# KT1025A.net
KiCad netlist of a schematic drawn in Altium Designer
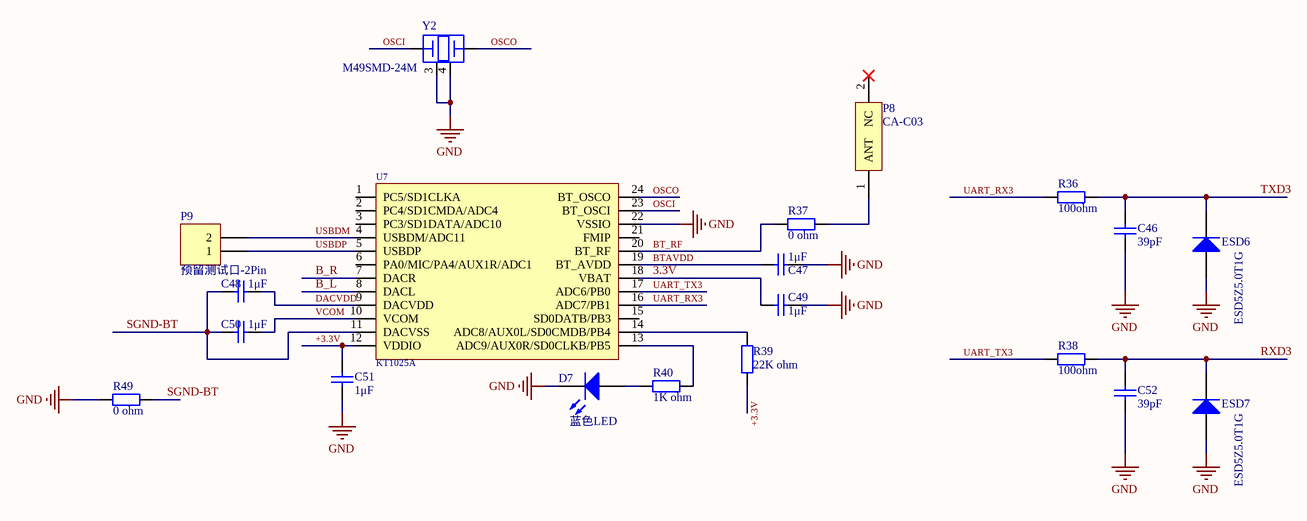
[diagram p0: KT1025A.SchDoc]

(export (version "E")
  (design (tool "Eeschema 10.0.6"))
  (components
    (comp (ref "C46")
      (value "39pF")
      (footprint "0603C")
      (description "39pF_50V,C0G (EIA),±1%")
      (libsource (lib "Yang_Lib") (part "Cap_39pF_50V_0603"))
    )
    (comp (ref "C47")
      (value "1μF")
      (footprint "0603C")
      (description "1μF_50V,X5R,±10%")
      (libsource (lib "Yang_Lib") (part "Cap_1μF_50V_0603"))
    )
    (comp (ref "C48")
      (value "1μF")
      (footprint "0603C")
      (description "1μF_50V,X5R,±10%")
      (libsource (lib "Yang_Lib") (part "Cap_1μF_50V_0603"))
    )
    (comp (ref "C49")
      (value "1μF")
      (footprint "0603C")
      (description "1μF_50V,X5R,±10%")
      (libsource (lib "Yang_Lib") (part "Cap_1μF_50V_0603"))
    )
    (comp (ref "C50")
      (value "1μF")
      (footprint "0603C")
      (description "1μF_50V,X5R,±10%")
      (libsource (lib "Yang_Lib") (part "Cap_1μF_50V_0603"))
    )
    (comp (ref "C51")
      (value "1μF")
      (footprint "0603C")
      (description "1μF_50V,X5R,±10%")
      (libsource (lib "Yang_Lib") (part "Cap_1μF_50V_0603"))
    )
    (comp (ref "C52")
      (value "39pF")
      (footprint "0603C")
      (description "39pF_50V,C0G (EIA),±1%")
      (libsource (lib "Yang_Lib") (part "Cap_39pF_50V_0603"))
    )
    (comp (ref "D7") (value "蓝色LED") (footprint "0603LED") (libsource (lib "Yang_Lib") (part "蓝色LED")))
    (comp (ref "ESD6")
      (value "ESD5Z5.0T1G")
      (footprint "SOD523")
      (libsource (lib "Yang_Lib") (part "ESD5Z5.0T1G_SOD523"))
    )
    (comp (ref "ESD7")
      (value "ESD5Z5.0T1G")
      (footprint "SOD523")
      (libsource (lib "Yang_Lib") (part "ESD5Z5.0T1G_SOD523"))
    )
    (comp (ref "P8") (value "CA-C03") (footprint "ANT") (libsource (lib "Yang_Lib") (part "CA-C03")))
    (comp (ref "P9")
      (value "预留测试口-2Pin")
      (footprint "预留测试口 2Pin")
      (libsource (lib "Yang_Lib") (part "预留测试口-2Pin"))
    )
    (comp (ref "R36")
      (value "100ohm")
      (footprint "0603R")
      (description "100 ohm_5%")
      (libsource (lib "Yang_Lib") (part "Res_100ohm_0603"))
    )
    (comp (ref "R37")
      (value "0 ohm")
      (footprint "0603R")
      (description "0 ohm,5%")
      (libsource (lib "Yang_Lib") (part "Res_0 ohm_0603"))
    )
    (comp (ref "R38")
      (value "100ohm")
      (footprint "0603R")
      (description "100 ohm_5%")
      (libsource (lib "Yang_Lib") (part "Res_100ohm_0603"))
    )
    (comp (ref "R39")
      (value "22K ohm")
      (footprint "0603R")
      (description "22K ohm,1%")
      (libsource (lib "Yang_Lib") (part "Res_22K ohm_0603"))
    )
    (comp (ref "R40")
      (value "1K ohm")
      (footprint "0603R")
      (description "1K ohm,1%")
      (libsource (lib "Yang_Lib") (part "Res_1K ohm_0603"))
    )
    (comp (ref "R49")
      (value "0 ohm")
      (footprint "0805R")
      (description "0 ohm,5%")
      (libsource (lib "Yang_Lib") (part "Res_0 ohm_0805"))
    )
    (comp (ref "U7") (value "KT1025A") (footprint "SSOP24") (libsource (lib "Yang_Lib") (part "KT1025A")))
    (comp (ref "Y2")
      (value "M49SMD-24M")
      (footprint "M49S")
      (libsource (lib "Yang_Lib") (part "M49SMD-24M-10ppm"))
    )
  )
  (nets
    (net (code "1") (name "/+3.3V") (class "Default")
      (node (ref "C51") (pin "2") (pinfunction "2_2") (pintype "passive"))
      (node (ref "R39") (pin "1") (pinfunction "1_1") (pintype "passive"))
      (node (ref "U7") (pin "12") (pinfunction "VDDIO_12") (pintype "passive"))
    )
    (net (code "2") (name "/3.3V") (class "Default")
      (node (ref "C49") (pin "1") (pinfunction "1_1") (pintype "passive"))
      (node (ref "U7") (pin "18") (pinfunction "VBAT_18") (pintype "passive"))
    )
    (net (code "3") (name "/BTAVDD") (class "Default")
      (node (ref "C47") (pin "1") (pinfunction "1_1") (pintype "passive"))
      (node (ref "U7") (pin "19") (pinfunction "BT_AVDD_19") (pintype "passive"))
    )
    (net (code "4") (name "/BT_RF") (class "Default")
      (node (ref "R37") (pin "1") (pinfunction "1_1") (pintype "passive"))
      (node (ref "U7") (pin "20") (pinfunction "BT_RF_20") (pintype "passive"))
    )
    (net (code "5") (name "/B_L") (class "Default")
      (node (ref "U7") (pin "8") (pinfunction "DACL_8") (pintype "passive"))
    )
    (net (code "6") (name "/B_R") (class "Default")
      (node (ref "U7") (pin "7") (pinfunction "DACR_7") (pintype "passive"))
    )
    (net (code "7") (name "/DACVDD") (class "Default")
      (node (ref "C48") (pin "2") (pinfunction "2_2") (pintype "passive"))
      (node (ref "U7") (pin "9") (pinfunction "DACVDD_9") (pintype "passive"))
    )
    (net (code "8") (name "/OSCI") (class "Default")
      (node (ref "U7") (pin "23") (pinfunction "BT_OSCI_23") (pintype "passive"))
      (node (ref "Y2") (pin "1") (pinfunction "1_1") (pintype "passive"))
    )
    (net (code "9") (name "/OSCO") (class "Default")
      (node (ref "U7") (pin "24") (pinfunction "BT_OSCO_24") (pintype "passive"))
      (node (ref "Y2") (pin "2") (pinfunction "2_2") (pintype "passive"))
    )
    (net (code "10") (name "/RXD3") (class "Default")
      (node (ref "C52") (pin "2") (pinfunction "2_2") (pintype "passive"))
      (node (ref "ESD7") (pin "2") (pinfunction "K_2") (pintype "passive"))
      (node (ref "R38") (pin "2") (pinfunction "2_2") (pintype "passive"))
    )
    (net (code "11") (name "/SGND-BT") (class "Default")
      (node (ref "C48") (pin "1") (pinfunction "1_1") (pintype "passive"))
      (node (ref "C50") (pin "1") (pinfunction "1_1") (pintype "passive"))
      (node (ref "R49") (pin "2") (pinfunction "2_2") (pintype "passive"))
      (node (ref "U7") (pin "11") (pinfunction "DACVSS_11") (pintype "passive"))
    )
    (net (code "12") (name "/TXD3") (class "Default")
      (node (ref "C46") (pin "2") (pinfunction "2_2") (pintype "passive"))
      (node (ref "ESD6") (pin "2") (pinfunction "K_2") (pintype "passive"))
      (node (ref "R36") (pin "2") (pinfunction "2_2") (pintype "passive"))
    )
    (net (code "13") (name "/UART_RX3") (class "Default")
      (node (ref "R36") (pin "1") (pinfunction "1_1") (pintype "passive"))
      (node (ref "U7") (pin "16") (pinfunction "ADC7/PB1_16") (pintype "passive"))
    )
    (net (code "14") (name "/UART_TX3") (class "Default")
      (node (ref "R38") (pin "1") (pinfunction "1_1") (pintype "passive"))
      (node (ref "U7") (pin "17") (pinfunction "ADC6/PB0_17") (pintype "passive"))
    )
    (net (code "15") (name "/USBDM") (class "Default")
      (node (ref "P9") (pin "2") (pinfunction "2_2") (pintype "passive"))
      (node (ref "U7") (pin "4") (pinfunction "USBDM/ADC11_4") (pintype "passive"))
    )
    (net (code "16") (name "/USBDP") (class "Default")
      (node (ref "P9") (pin "1") (pinfunction "1_1") (pintype "passive"))
      (node (ref "U7") (pin "5") (pinfunction "USBDP_5") (pintype "passive"))
    )
    (net (code "17") (name "/VCOM") (class "Default")
      (node (ref "C50") (pin "2") (pinfunction "2_2") (pintype "passive"))
      (node (ref "U7") (pin "10") (pinfunction "VCOM_10") (pintype "passive"))
    )
    (net (code "18") (name "GND") (class "Default")
      (node (ref "C46") (pin "1") (pinfunction "1_1") (pintype "passive"))
      (node (ref "C47") (pin "2") (pinfunction "2_2") (pintype "passive"))
      (node (ref "C49") (pin "2") (pinfunction "2_2") (pintype "passive"))
      (node (ref "C51") (pin "1") (pinfunction "1_1") (pintype "passive"))
      (node (ref "C52") (pin "1") (pinfunction "1_1") (pintype "passive"))
      (node (ref "D7") (pin "2") (pinfunction "K_2") (pintype "passive"))
      (node (ref "ESD6") (pin "1") (pinfunction "A_1") (pintype "passive"))
      (node (ref "ESD7") (pin "1") (pinfunction "A_1") (pintype "passive"))
      (node (ref "R49") (pin "1") (pinfunction "1_1") (pintype "passive"))
      (node (ref "U7") (pin "22") (pinfunction "VSSIO_22") (pintype "passive"))
      (node (ref "Y2") (pin "3") (pintype "passive"))
      (node (ref "Y2") (pin "4") (pintype "passive"))
    )
    (net (code "19") (name "Net-(D7-A)") (class "Default")
      (node (ref "D7") (pin "1") (pinfunction "A_1") (pintype "passive"))
      (node (ref "R40") (pin "2") (pinfunction "2_2") (pintype "passive"))
    )
    (net (code "20") (name "Net-(P8-ANT)") (class "Default")
      (node (ref "P8") (pin "1") (pinfunction "ANT_1") (pintype "passive"))
      (node (ref "R37") (pin "2") (pinfunction "2_2") (pintype "passive"))
    )
    (net (code "21") (name "Net-(U7-ADC8{slash}AUX0L{slash}SD0CMDB{slash}PB4)") (class "Default")
      (node (ref "R39") (pin "2") (pinfunction "2_2") (pintype "passive"))
      (node (ref "U7") (pin "14") (pinfunction "ADC8/AUX0L/SD0CMDB/PB4_14") (pintype "passive"))
    )
    (net (code "22") (name "Net-(U7-ADC9{slash}AUX0R{slash}SD0CLKB{slash}PB5)") (class "Default")
      (node (ref "R40") (pin "1") (pinfunction "1_1") (pintype "passive"))
      (node (ref "U7") (pin "13") (pinfunction "ADC9/AUX0R/SD0CLKB/PB5_13") (pintype "passive"))
    )
    (net (code "23") (name "unconnected-(P8-NC-Pad2)") (class "Default")
      (node (ref "P8") (pin "2") (pinfunction "NC_2") (pintype "passive+no_connect"))
    )
    (net (code "24") (name "unconnected-(U7-FMIP-Pad21)") (class "Default")
      (node (ref "U7") (pin "21") (pinfunction "FMIP_21") (pintype "passive"))
    )
    (net (code "25") (name "unconnected-(U7-PA0{slash}MIC{slash}PA4{slash}AUX1R{slash}ADC1-Pad6)") (class "Default")
      (node (ref "U7") (pin "6") (pinfunction "PA0/MIC/PA4/AUX1R/ADC1_6") (pintype "passive"))
    )
    (net (code "26") (name "unconnected-(U7-PC3{slash}SD1DATA{slash}ADC10-Pad3)") (class "Default")
      (node (ref "U7") (pin "3") (pinfunction "PC3/SD1DATA/ADC10_3") (pintype "passive"))
    )
    (net (code "27") (name "unconnected-(U7-PC4{slash}SD1CMDA{slash}ADC4-Pad2)") (class "Default")
      (node (ref "U7") (pin "2") (pinfunction "PC4/SD1CMDA/ADC4_2") (pintype "passive"))
    )
    (net (code "28") (name "unconnected-(U7-PC5{slash}SD1CLKA-Pad1)") (class "Default")
      (node (ref "U7") (pin "1") (pinfunction "PC5/SD1CLKA_1") (pintype "passive"))
    )
    (net (code "29") (name "unconnected-(U7-SD0DATB{slash}PB3-Pad15)") (class "Default")
      (node (ref "U7") (pin "15") (pinfunction "SD0DATB/PB3_15") (pintype "passive"))
    )
  )
)
